# Sheet2.net
KiCad netlist of a schematic drawn in Altium Designer
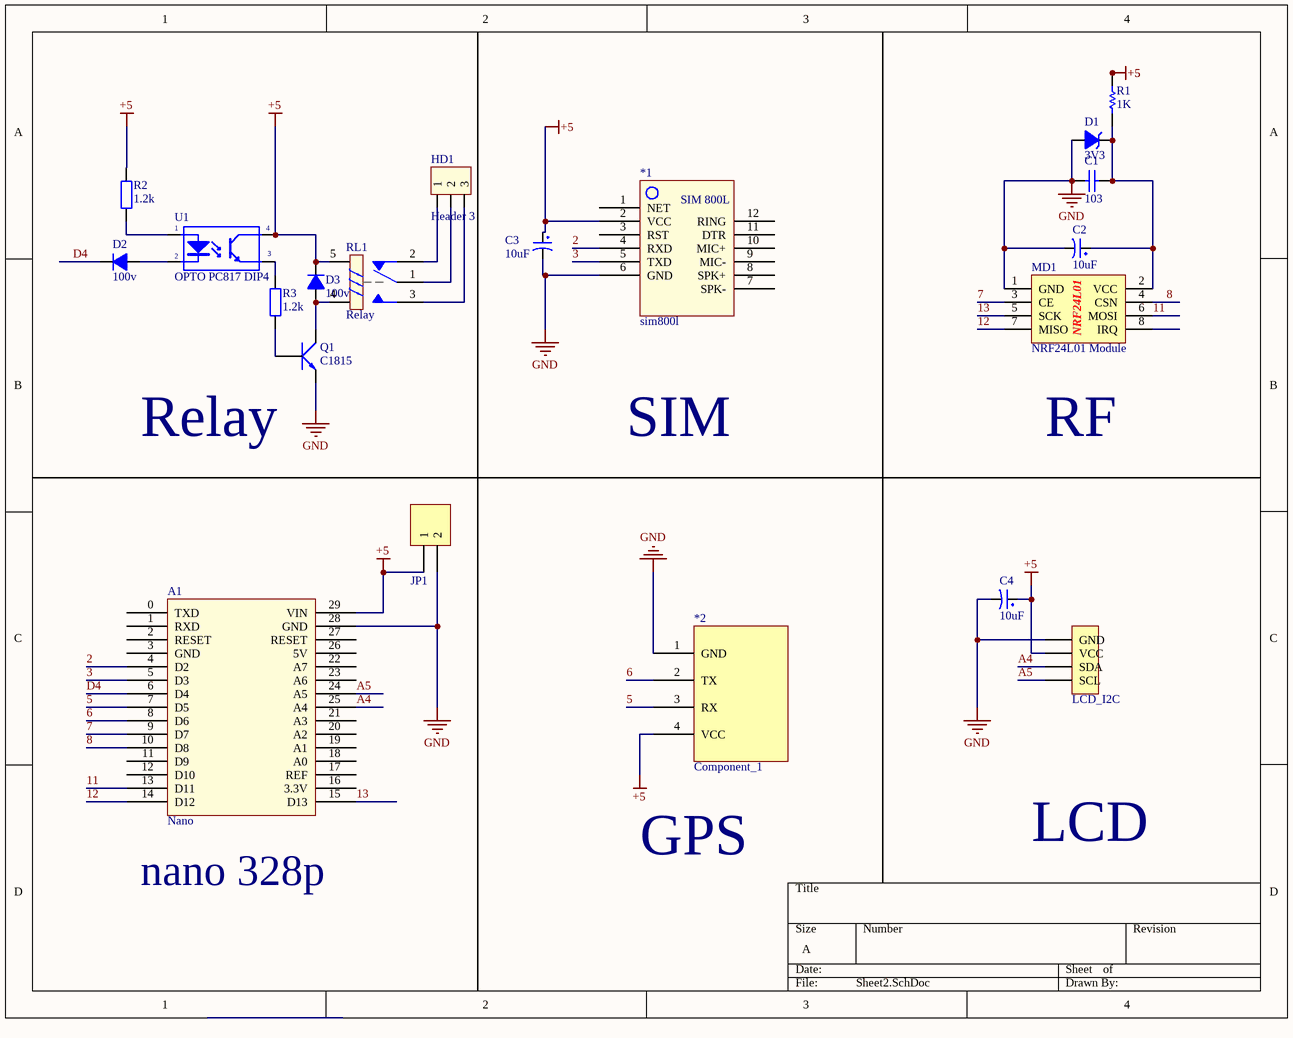
[diagram p0: Sheet2.SchDoc]

(export (version "E")
  (design (tool "Eeschema 10.0.6"))
  (components
    (comp (ref "*1")
      (value "sim800l")
      (footprint "SIM 800L")
      (libsource (lib "Integrated_Library1") (part "sim800l"))
    )
    (comp (ref "*2")
      (value "Component_1")
      (footprint "NEO6M - duplicate1")
      (libsource (lib "Neo6M") (part "Component_1"))
    )
    (comp (ref "A1")
      (value "Nano")
      (footprint "Arduino nano")
      (libsource (lib "Altium_Lib_by_KhueNguyenCreator") (part "Arduino Nano"))
    )
    (comp (ref "C1")
      (value "103")
      (footprint "tu gom")
      (description "Cắm")
      (libsource (lib "Altium_Lib_by_KhueNguyenCreator") (part "Tu gom 103 50V"))
    )
    (comp (ref "C2")
      (value "10uF")
      (footprint "tu hoa 4mm")
      (description "Cắm")
      (libsource (lib "Altium_Lib_by_KhueNguyenCreator") (part "Tu Hoa 10uF 16V 4x7"))
    )
    (comp (ref "C3")
      (value "10uF")
      (footprint "tu hoa 4mm")
      (description "Cắm")
      (libsource (lib "") (part "Tu Hoa 10uF 16V 4x7_1"))
    )
    (comp (ref "C4")
      (value "10uF")
      (footprint "tu hoa 4mm")
      (description "Cắm")
      (libsource (lib "Altium_Lib_by_KhueNguyenCreator") (part "Tu Hoa 10uF 16V 4x7"))
    )
    (comp (ref "D1")
      (value "3V3")
      (footprint "DZ0.5A")
      (description "Diode Zenner")
      (libsource (lib "syhaunguyen") (part "DZ"))
    )
    (comp (ref "D2")
      (value "100v")
      (footprint "DIODE 1A")
      (description "Cắm")
      (libsource (lib "Altium_Lib_by_KhueNguyenCreator") (part "Diode 1N4007"))
    )
    (comp (ref "D3")
      (value "100v")
      (footprint "DIODE 1A")
      (description "Cắm")
      (libsource (lib "Altium_Lib_by_KhueNguyenCreator") (part "Diode 1N4007"))
    )
    (comp (ref "H1")
      (value "LCD_I2C")
      (footprint "XH2.54M-4")
      (description "Cắm")
      (libsource (lib "Altium_Lib_by_KhueNguyenCreator") (part "Header 4P 2.54 Duc Thang"))
    )
    (comp (ref "HD1")
      (value "Header 3")
      (footprint "HED3")
      (description "Header 3 (Green)")
      (libsource (lib "syhaunguyen") (part "Hed3"))
    )
    (comp (ref "JP1")
      (value "Header 2_1")
      (footprint "HED2")
      (description "Header, 2-Pin")
      (fields (field (name "MANUFACTURER") "Generic Components"))
      (libsource (lib "syhaunguyen") (part "Header 2_1"))
    )
    (comp (ref "MD1")
      (value "NRF24L01 Module")
      (footprint "NRF24L01")
      (libsource (lib "Altium_Lib_by_KhueNguyenCreator") (part "NRF24L01 Module"))
    )
    (comp (ref "Q1")
      (value "C1815")
      (footprint "TO92")
      (description "NPN transistor")
      (libsource (lib "Altium_Lib_by_KhueNguyenCreator") (part "C1815"))
    )
    (comp (ref "R1")
      (value "1K")
      (footprint "R1/4W")
      (description "Resistor")
      (fields
        (field (name "MANUFACTURER") "Generic Components")
        (field (name "Comment") "Res1")
        (field (name "PUBLISHER") "Altium Hobart Technology Centre")
      )
      (libsource (lib "syhaunguyen") (part "Res1_4"))
    )
    (comp (ref "R2")
      (value "1.2k")
      (footprint "tro vach 1/4w")
      (description "Cắm")
      (libsource (lib "Altium_Lib_by_KhueNguyenCreator") (part "Tro Vach 1/4W 5% 1.2k"))
    )
    (comp (ref "R3")
      (value "1.2k")
      (footprint "tro vach 1/4w")
      (description "Cắm")
      (libsource (lib "Altium_Lib_by_KhueNguyenCreator") (part "Tro Vach 1/4W 5% 1.2k"))
    )
    (comp (ref "RL1")
      (value "Relay")
      (footprint "Relay 5 Chan SRD")
      (description "Relay 5 Chan")
      (libsource (lib "Altium_Lib_by_KhueNguyenCreator") (part "Relay 5 Chan SRD"))
    )
    (comp (ref "U1")
      (value "OPTO PC817 DIP4")
      (footprint "DIP4")
      (description "Single Opto")
      (libsource (lib "Altium_Lib_by_KhueNguyenCreator") (part "OPTO PC817 DIP4"))
    )
  )
  (nets
    (net (code "1") (name "+5") (class "Default")
      (node (ref "*1") (pin "2") (pinfunction "VCC_2") (pintype "passive"))
      (node (ref "*2") (pin "4") (pinfunction "VCC_4") (pintype "passive"))
      (node (ref "A1") (pin "29") (pinfunction "VIN_29") (pintype "passive"))
      (node (ref "C3") (pin "1") (pinfunction "1_1") (pintype "passive"))
      (node (ref "C4") (pin "1") (pinfunction "1_1") (pintype "passive"))
      (node (ref "D3") (pin "2") (pinfunction "K_2") (pintype "passive"))
      (node (ref "H1") (pin "2") (pinfunction "VCC_2") (pintype "passive"))
      (node (ref "JP1") (pin "1") (pinfunction "1_1") (pintype "passive"))
      (node (ref "R1") (pin "2") (pinfunction "2_2") (pintype "passive"))
      (node (ref "R2") (pin "1") (pinfunction "1_1") (pintype "passive"))
      (node (ref "RL1") (pin "5") (pinfunction "5_5") (pintype "passive"))
      (node (ref "U1") (pin "4") (pinfunction "C_4") (pintype "passive"))
    )
    (net (code "2") (name "/2") (class "Default")
      (node (ref "*1") (pin "4") (pinfunction "RXD_4") (pintype "passive"))
      (node (ref "A1") (pin "4") (pinfunction "D2_4") (pintype "passive"))
    )
    (net (code "3") (name "/3") (class "Default")
      (node (ref "*1") (pin "5") (pinfunction "TXD_5") (pintype "passive"))
      (node (ref "A1") (pin "5") (pinfunction "D3_5") (pintype "passive"))
    )
    (net (code "4") (name "/5") (class "Default")
      (node (ref "*2") (pin "3") (pinfunction "RX_3") (pintype "passive"))
      (node (ref "A1") (pin "7") (pinfunction "D5_7") (pintype "passive"))
    )
    (net (code "5") (name "/6") (class "Default")
      (node (ref "*2") (pin "2") (pinfunction "TX_2") (pintype "passive"))
      (node (ref "A1") (pin "8") (pinfunction "D6_8") (pintype "passive"))
    )
    (net (code "6") (name "/7") (class "Default")
      (node (ref "A1") (pin "9") (pinfunction "D7_9") (pintype "passive"))
      (node (ref "MD1") (pin "3") (pinfunction "CE_3") (pintype "passive"))
    )
    (net (code "7") (name "/8") (class "Default")
      (node (ref "A1") (pin "10") (pinfunction "D8_10") (pintype "passive"))
      (node (ref "MD1") (pin "4") (pinfunction "CSN_4") (pintype "passive"))
    )
    (net (code "8") (name "/11") (class "Default")
      (node (ref "A1") (pin "13") (pinfunction "D11_13") (pintype "passive"))
      (node (ref "MD1") (pin "6") (pinfunction "MOSI_6") (pintype "passive"))
    )
    (net (code "9") (name "/12") (class "Default")
      (node (ref "A1") (pin "14") (pinfunction "D12_14") (pintype "passive"))
      (node (ref "MD1") (pin "7") (pinfunction "MISO_7") (pintype "passive"))
    )
    (net (code "10") (name "/13") (class "Default")
      (node (ref "A1") (pin "15") (pinfunction "D13_15") (pintype "passive"))
      (node (ref "MD1") (pin "5") (pinfunction "SCK_5") (pintype "passive"))
    )
    (net (code "11") (name "/A4") (class "Default")
      (node (ref "A1") (pin "25") (pinfunction "A4_25") (pintype "passive"))
      (node (ref "H1") (pin "3") (pinfunction "SDA_3") (pintype "passive"))
    )
    (net (code "12") (name "/A5") (class "Default")
      (node (ref "A1") (pin "24") (pinfunction "A5_24") (pintype "passive"))
      (node (ref "H1") (pin "4") (pinfunction "SCL_4") (pintype "passive"))
    )
    (net (code "13") (name "/D4") (class "Default")
      (node (ref "A1") (pin "6") (pinfunction "D4_6") (pintype "passive"))
      (node (ref "D2") (pin "2") (pinfunction "K_2") (pintype "passive"))
    )
    (net (code "14") (name "GND") (class "Default")
      (node (ref "*1") (pin "6") (pinfunction "GND_6") (pintype "passive"))
      (node (ref "*2") (pin "1") (pinfunction "GND_1") (pintype "passive"))
      (node (ref "A1") (pin "28") (pinfunction "GND_28") (pintype "passive"))
      (node (ref "C1") (pin "2") (pinfunction "2_2") (pintype "passive"))
      (node (ref "C2") (pin "2") (pinfunction "2_2") (pintype "passive"))
      (node (ref "C3") (pin "2") (pinfunction "2_2") (pintype "passive"))
      (node (ref "C4") (pin "2") (pinfunction "2_2") (pintype "passive"))
      (node (ref "D1") (pin "1") (pinfunction "A_1") (pintype "passive"))
      (node (ref "H1") (pin "1") (pinfunction "GND_1") (pintype "passive"))
      (node (ref "JP1") (pin "2") (pinfunction "2_2") (pintype "passive"))
      (node (ref "MD1") (pin "1") (pinfunction "GND_1") (pintype "passive"))
      (node (ref "Q1") (pin "1") (pinfunction "E_1") (pintype "passive"))
    )
    (net (code "15") (name "Net-(D1-K)") (class "Default")
      (node (ref "C1") (pin "1") (pinfunction "1_1") (pintype "passive"))
      (node (ref "C2") (pin "1") (pinfunction "1_1") (pintype "passive"))
      (node (ref "D1") (pin "2") (pinfunction "K_2") (pintype "passive"))
      (node (ref "MD1") (pin "2") (pinfunction "VCC_2") (pintype "passive"))
      (node (ref "R1") (pin "1") (pinfunction "1_1") (pintype "passive"))
    )
    (net (code "16") (name "Net-(D2-A)") (class "Default")
      (node (ref "D2") (pin "1") (pinfunction "A_1") (pintype "passive"))
      (node (ref "U1") (pin "2") (pinfunction "K_2") (pintype "passive"))
    )
    (net (code "17") (name "Net-(D3-A)") (class "Default")
      (node (ref "D3") (pin "1") (pinfunction "A_1") (pintype "passive"))
      (node (ref "Q1") (pin "2") (pinfunction "C_2") (pintype "passive"))
      (node (ref "RL1") (pin "4") (pinfunction "4_4") (pintype "passive"))
    )
    (net (code "18") (name "Net-(HD1-Pad1)") (class "Default")
      (node (ref "HD1") (pin "1") (pinfunction "1_1") (pintype "passive"))
      (node (ref "RL1") (pin "2") (pinfunction "2_2") (pintype "passive"))
    )
    (net (code "19") (name "Net-(HD1-Pad2)") (class "Default")
      (node (ref "HD1") (pin "2") (pinfunction "2_2") (pintype "passive"))
      (node (ref "RL1") (pin "1") (pinfunction "1_1") (pintype "passive"))
    )
    (net (code "20") (name "Net-(HD1-Pad3)") (class "Default")
      (node (ref "HD1") (pin "3") (pinfunction "3_3") (pintype "passive"))
      (node (ref "RL1") (pin "3") (pinfunction "3_3") (pintype "passive"))
    )
    (net (code "21") (name "Net-(Q1-B)") (class "Default")
      (node (ref "Q1") (pin "3") (pinfunction "B_3") (pintype "passive"))
      (node (ref "R3") (pin "2") (pinfunction "2_2") (pintype "passive"))
    )
    (net (code "22") (name "Net-(U1-A)") (class "Default")
      (node (ref "R2") (pin "2") (pinfunction "2_2") (pintype "passive"))
      (node (ref "U1") (pin "1") (pinfunction "A_1") (pintype "passive"))
    )
    (net (code "23") (name "Net-(U1-E)") (class "Default")
      (node (ref "R3") (pin "1") (pinfunction "1_1") (pintype "passive"))
      (node (ref "U1") (pin "3") (pinfunction "E_3") (pintype "passive"))
    )
    (net (code "24") (name "unconnected-(*1-DTR-Pad11)") (class "Default")
      (node (ref "*1") (pin "11") (pinfunction "DTR_11") (pintype "passive"))
    )
    (net (code "25") (name "unconnected-(*1-MIC+-Pad10)") (class "Default")
      (node (ref "*1") (pin "10") (pinfunction "MIC+_10") (pintype "passive"))
    )
    (net (code "26") (name "unconnected-(*1-MIC--Pad9)") (class "Default")
      (node (ref "*1") (pin "9") (pinfunction "MIC-_9") (pintype "passive"))
    )
    (net (code "27") (name "unconnected-(*1-NET-Pad1)") (class "Default")
      (node (ref "*1") (pin "1") (pinfunction "NET_1") (pintype "passive"))
    )
    (net (code "28") (name "unconnected-(*1-RING-Pad12)") (class "Default")
      (node (ref "*1") (pin "12") (pinfunction "RING_12") (pintype "passive"))
    )
    (net (code "29") (name "unconnected-(*1-RST-Pad3)") (class "Default")
      (node (ref "*1") (pin "3") (pinfunction "RST_3") (pintype "passive"))
    )
    (net (code "30") (name "unconnected-(*1-SPK+-Pad8)") (class "Default")
      (node (ref "*1") (pin "8") (pinfunction "SPK+_8") (pintype "passive"))
    )
    (net (code "31") (name "unconnected-(*1-SPK--Pad7)") (class "Default")
      (node (ref "*1") (pin "7") (pinfunction "SPK-_7") (pintype "passive"))
    )
    (net (code "32") (name "unconnected-(A1-3.3V-Pad16)") (class "Default")
      (node (ref "A1") (pin "16") (pinfunction "3.3V_16") (pintype "passive"))
    )
    (net (code "33") (name "unconnected-(A1-5V-Pad26)") (class "Default")
      (node (ref "A1") (pin "26") (pinfunction "5V_26") (pintype "passive"))
    )
    (net (code "34") (name "unconnected-(A1-A0-Pad18)") (class "Default")
      (node (ref "A1") (pin "18") (pinfunction "A0_18") (pintype "passive"))
    )
    (net (code "35") (name "unconnected-(A1-A1-Pad19)") (class "Default")
      (node (ref "A1") (pin "19") (pinfunction "A1_19") (pintype "passive"))
    )
    (net (code "36") (name "unconnected-(A1-A2-Pad20)") (class "Default")
      (node (ref "A1") (pin "20") (pinfunction "A2_20") (pintype "passive"))
    )
    (net (code "37") (name "unconnected-(A1-A3-Pad21)") (class "Default")
      (node (ref "A1") (pin "21") (pinfunction "A3_21") (pintype "passive"))
    )
    (net (code "38") (name "unconnected-(A1-A6-Pad23)") (class "Default")
      (node (ref "A1") (pin "23") (pinfunction "A6_23") (pintype "passive"))
    )
    (net (code "39") (name "unconnected-(A1-A7-Pad22)") (class "Default")
      (node (ref "A1") (pin "22") (pinfunction "A7_22") (pintype "passive"))
    )
    (net (code "40") (name "unconnected-(A1-D9-Pad11)") (class "Default")
      (node (ref "A1") (pin "11") (pinfunction "D9_11") (pintype "passive"))
    )
    (net (code "41") (name "unconnected-(A1-D10-Pad12)") (class "Default")
      (node (ref "A1") (pin "12") (pinfunction "D10_12") (pintype "passive"))
    )
    (net (code "42") (name "unconnected-(A1-GND-Pad3)") (class "Default")
      (node (ref "A1") (pin "3") (pinfunction "GND_3") (pintype "passive"))
    )
    (net (code "43") (name "unconnected-(A1-REF-Pad17)") (class "Default")
      (node (ref "A1") (pin "17") (pinfunction "REF_17") (pintype "passive"))
    )
    (net (code "44") (name "unconnected-(A1-RESET-Pad2)") (class "Default")
      (node (ref "A1") (pin "2") (pinfunction "RESET_2") (pintype "passive"))
    )
    (net (code "45") (name "unconnected-(A1-RESET-Pad27)") (class "Default")
      (node (ref "A1") (pin "27") (pinfunction "RESET_27") (pintype "passive"))
    )
    (net (code "46") (name "unconnected-(A1-RXD-Pad1)") (class "Default")
      (node (ref "A1") (pin "1") (pinfunction "RXD_1") (pintype "passive"))
    )
    (net (code "47") (name "unconnected-(A1-TXD-Pad0)") (class "Default")
      (node (ref "A1") (pin "0") (pinfunction "TXD_0") (pintype "passive"))
    )
    (net (code "48") (name "unconnected-(MD1-IRQ-Pad8)") (class "Default")
      (node (ref "MD1") (pin "8") (pinfunction "IRQ_8") (pintype "passive"))
    )
  )
)
